# LED2.net
KiCad netlist of a schematic drawn in Altium Designer
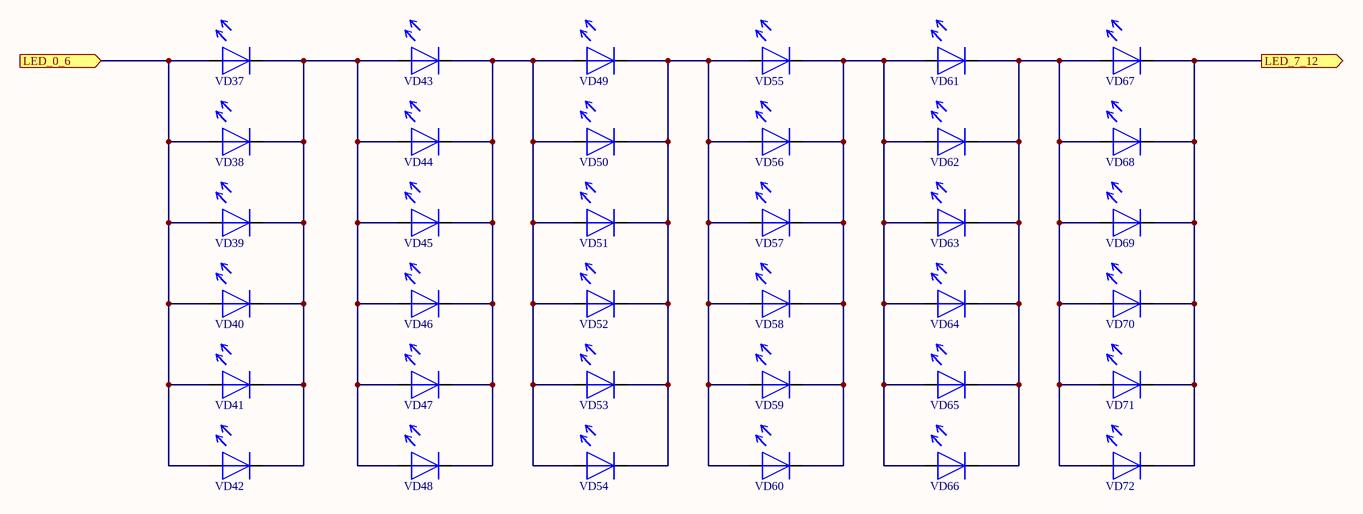
[diagram p0: LED2.SchDoc]

(export (version "E")
  (design (tool "Eeschema 10.0.6"))
  (components
    (comp (ref "VD37")
      (value "SPMWHT541MD5WAT0SB")
      (footprint "LED_Samsung")
      (libsource (lib "gprs_modem_2") (part "LED SPMWHT541MD5WAT0SB"))
    )
    (comp (ref "VD38")
      (value "SPMWHT541MD5WAT0SB")
      (footprint "LED_Samsung")
      (libsource (lib "gprs_modem_2") (part "LED SPMWHT541MD5WAT0SB"))
    )
    (comp (ref "VD39")
      (value "SPMWHT541MD5WAT0SB")
      (footprint "LED_Samsung")
      (libsource (lib "gprs_modem_2") (part "LED SPMWHT541MD5WAT0SB"))
    )
    (comp (ref "VD40")
      (value "SPMWHT541MD5WAT0SB")
      (footprint "LED_Samsung")
      (libsource (lib "gprs_modem_2") (part "LED SPMWHT541MD5WAT0SB"))
    )
    (comp (ref "VD41")
      (value "SPMWHT541MD5WAT0SB")
      (footprint "LED_Samsung")
      (libsource (lib "gprs_modem_2") (part "LED SPMWHT541MD5WAT0SB"))
    )
    (comp (ref "VD42")
      (value "SPMWHT541MD5WAT0SB")
      (footprint "LED_Samsung")
      (libsource (lib "gprs_modem_2") (part "LED SPMWHT541MD5WAT0SB"))
    )
    (comp (ref "VD43")
      (value "SPMWHT541MD5WAT0SB")
      (footprint "LED_Samsung")
      (libsource (lib "gprs_modem_2") (part "LED SPMWHT541MD5WAT0SB"))
    )
    (comp (ref "VD44")
      (value "SPMWHT541MD5WAT0SB")
      (footprint "LED_Samsung")
      (libsource (lib "gprs_modem_2") (part "LED SPMWHT541MD5WAT0SB"))
    )
    (comp (ref "VD45")
      (value "SPMWHT541MD5WAT0SB")
      (footprint "LED_Samsung")
      (libsource (lib "gprs_modem_2") (part "LED SPMWHT541MD5WAT0SB"))
    )
    (comp (ref "VD46")
      (value "SPMWHT541MD5WAT0SB")
      (footprint "LED_Samsung")
      (libsource (lib "gprs_modem_2") (part "LED SPMWHT541MD5WAT0SB"))
    )
    (comp (ref "VD47")
      (value "SPMWHT541MD5WAT0SB")
      (footprint "LED_Samsung")
      (libsource (lib "gprs_modem_2") (part "LED SPMWHT541MD5WAT0SB"))
    )
    (comp (ref "VD48")
      (value "SPMWHT541MD5WAT0SB")
      (footprint "LED_Samsung")
      (libsource (lib "gprs_modem_2") (part "LED SPMWHT541MD5WAT0SB"))
    )
    (comp (ref "VD49")
      (value "SPMWHT541MD5WAT0SB")
      (footprint "LED_Samsung")
      (libsource (lib "gprs_modem_2") (part "LED SPMWHT541MD5WAT0SB"))
    )
    (comp (ref "VD50")
      (value "SPMWHT541MD5WAT0SB")
      (footprint "LED_Samsung")
      (libsource (lib "gprs_modem_2") (part "LED SPMWHT541MD5WAT0SB"))
    )
    (comp (ref "VD51")
      (value "SPMWHT541MD5WAT0SB")
      (footprint "LED_Samsung")
      (libsource (lib "gprs_modem_2") (part "LED SPMWHT541MD5WAT0SB"))
    )
    (comp (ref "VD52")
      (value "SPMWHT541MD5WAT0SB")
      (footprint "LED_Samsung")
      (libsource (lib "gprs_modem_2") (part "LED SPMWHT541MD5WAT0SB"))
    )
    (comp (ref "VD53")
      (value "SPMWHT541MD5WAT0SB")
      (footprint "LED_Samsung")
      (libsource (lib "gprs_modem_2") (part "LED SPMWHT541MD5WAT0SB"))
    )
    (comp (ref "VD54")
      (value "SPMWHT541MD5WAT0SB")
      (footprint "LED_Samsung")
      (libsource (lib "gprs_modem_2") (part "LED SPMWHT541MD5WAT0SB"))
    )
    (comp (ref "VD55")
      (value "SPMWHT541MD5WAT0SB")
      (footprint "LED_Samsung")
      (libsource (lib "gprs_modem_2") (part "LED SPMWHT541MD5WAT0SB"))
    )
    (comp (ref "VD56")
      (value "SPMWHT541MD5WAT0SB")
      (footprint "LED_Samsung")
      (libsource (lib "gprs_modem_2") (part "LED SPMWHT541MD5WAT0SB"))
    )
    (comp (ref "VD57")
      (value "SPMWHT541MD5WAT0SB")
      (footprint "LED_Samsung")
      (libsource (lib "gprs_modem_2") (part "LED SPMWHT541MD5WAT0SB"))
    )
    (comp (ref "VD58")
      (value "SPMWHT541MD5WAT0SB")
      (footprint "LED_Samsung")
      (libsource (lib "gprs_modem_2") (part "LED SPMWHT541MD5WAT0SB"))
    )
    (comp (ref "VD59")
      (value "SPMWHT541MD5WAT0SB")
      (footprint "LED_Samsung")
      (libsource (lib "gprs_modem_2") (part "LED SPMWHT541MD5WAT0SB"))
    )
    (comp (ref "VD60")
      (value "SPMWHT541MD5WAT0SB")
      (footprint "LED_Samsung")
      (libsource (lib "gprs_modem_2") (part "LED SPMWHT541MD5WAT0SB"))
    )
    (comp (ref "VD61")
      (value "SPMWHT541MD5WAT0SB")
      (footprint "LED_Samsung")
      (libsource (lib "gprs_modem_2") (part "LED SPMWHT541MD5WAT0SB"))
    )
    (comp (ref "VD62")
      (value "SPMWHT541MD5WAT0SB")
      (footprint "LED_Samsung")
      (libsource (lib "gprs_modem_2") (part "LED SPMWHT541MD5WAT0SB"))
    )
    (comp (ref "VD63")
      (value "SPMWHT541MD5WAT0SB")
      (footprint "LED_Samsung")
      (libsource (lib "gprs_modem_2") (part "LED SPMWHT541MD5WAT0SB"))
    )
    (comp (ref "VD64")
      (value "SPMWHT541MD5WAT0SB")
      (footprint "LED_Samsung")
      (libsource (lib "gprs_modem_2") (part "LED SPMWHT541MD5WAT0SB"))
    )
    (comp (ref "VD65")
      (value "SPMWHT541MD5WAT0SB")
      (footprint "LED_Samsung")
      (libsource (lib "gprs_modem_2") (part "LED SPMWHT541MD5WAT0SB"))
    )
    (comp (ref "VD66")
      (value "SPMWHT541MD5WAT0SB")
      (footprint "LED_Samsung")
      (libsource (lib "gprs_modem_2") (part "LED SPMWHT541MD5WAT0SB"))
    )
    (comp (ref "VD67")
      (value "SPMWHT541MD5WAT0SB")
      (footprint "LED_Samsung")
      (libsource (lib "gprs_modem_2") (part "LED SPMWHT541MD5WAT0SB"))
    )
    (comp (ref "VD68")
      (value "SPMWHT541MD5WAT0SB")
      (footprint "LED_Samsung")
      (libsource (lib "gprs_modem_2") (part "LED SPMWHT541MD5WAT0SB"))
    )
    (comp (ref "VD69")
      (value "SPMWHT541MD5WAT0SB")
      (footprint "LED_Samsung")
      (libsource (lib "gprs_modem_2") (part "LED SPMWHT541MD5WAT0SB"))
    )
    (comp (ref "VD70")
      (value "SPMWHT541MD5WAT0SB")
      (footprint "LED_Samsung")
      (libsource (lib "gprs_modem_2") (part "LED SPMWHT541MD5WAT0SB"))
    )
    (comp (ref "VD71")
      (value "SPMWHT541MD5WAT0SB")
      (footprint "LED_Samsung")
      (libsource (lib "gprs_modem_2") (part "LED SPMWHT541MD5WAT0SB"))
    )
    (comp (ref "VD72")
      (value "SPMWHT541MD5WAT0SB")
      (footprint "LED_Samsung")
      (libsource (lib "gprs_modem_2") (part "LED SPMWHT541MD5WAT0SB"))
    )
  )
  (nets
    (net (code "1") (name "/LED_0_6") (class "Default")
      (node (ref "VD37") (pin "1") (pintype "passive"))
      (node (ref "VD38") (pin "1") (pintype "passive"))
      (node (ref "VD39") (pin "1") (pintype "passive"))
      (node (ref "VD40") (pin "1") (pintype "passive"))
      (node (ref "VD41") (pin "1") (pintype "passive"))
      (node (ref "VD42") (pin "1") (pintype "passive"))
    )
    (net (code "2") (name "/LED_7_12") (class "Default")
      (node (ref "VD67") (pin "2") (pintype "passive"))
      (node (ref "VD68") (pin "2") (pintype "passive"))
      (node (ref "VD69") (pin "2") (pintype "passive"))
      (node (ref "VD70") (pin "2") (pintype "passive"))
      (node (ref "VD71") (pin "2") (pintype "passive"))
      (node (ref "VD72") (pin "2") (pintype "passive"))
    )
    (net (code "3") (name "Net-(VD37-Pad2)") (class "Default")
      (node (ref "VD37") (pin "2") (pintype "passive"))
      (node (ref "VD38") (pin "2") (pintype "passive"))
      (node (ref "VD39") (pin "2") (pintype "passive"))
      (node (ref "VD40") (pin "2") (pintype "passive"))
      (node (ref "VD41") (pin "2") (pintype "passive"))
      (node (ref "VD42") (pin "2") (pintype "passive"))
      (node (ref "VD43") (pin "1") (pintype "passive"))
      (node (ref "VD44") (pin "1") (pintype "passive"))
      (node (ref "VD45") (pin "1") (pintype "passive"))
      (node (ref "VD46") (pin "1") (pintype "passive"))
      (node (ref "VD47") (pin "1") (pintype "passive"))
      (node (ref "VD48") (pin "1") (pintype "passive"))
    )
    (net (code "4") (name "Net-(VD43-Pad2)") (class "Default")
      (node (ref "VD43") (pin "2") (pintype "passive"))
      (node (ref "VD44") (pin "2") (pintype "passive"))
      (node (ref "VD45") (pin "2") (pintype "passive"))
      (node (ref "VD46") (pin "2") (pintype "passive"))
      (node (ref "VD47") (pin "2") (pintype "passive"))
      (node (ref "VD48") (pin "2") (pintype "passive"))
      (node (ref "VD49") (pin "1") (pintype "passive"))
      (node (ref "VD50") (pin "1") (pintype "passive"))
      (node (ref "VD51") (pin "1") (pintype "passive"))
      (node (ref "VD52") (pin "1") (pintype "passive"))
      (node (ref "VD53") (pin "1") (pintype "passive"))
      (node (ref "VD54") (pin "1") (pintype "passive"))
    )
    (net (code "5") (name "Net-(VD49-Pad2)") (class "Default")
      (node (ref "VD49") (pin "2") (pintype "passive"))
      (node (ref "VD50") (pin "2") (pintype "passive"))
      (node (ref "VD51") (pin "2") (pintype "passive"))
      (node (ref "VD52") (pin "2") (pintype "passive"))
      (node (ref "VD53") (pin "2") (pintype "passive"))
      (node (ref "VD54") (pin "2") (pintype "passive"))
      (node (ref "VD55") (pin "1") (pintype "passive"))
      (node (ref "VD56") (pin "1") (pintype "passive"))
      (node (ref "VD57") (pin "1") (pintype "passive"))
      (node (ref "VD58") (pin "1") (pintype "passive"))
      (node (ref "VD59") (pin "1") (pintype "passive"))
      (node (ref "VD60") (pin "1") (pintype "passive"))
    )
    (net (code "6") (name "Net-(VD55-Pad2)") (class "Default")
      (node (ref "VD55") (pin "2") (pintype "passive"))
      (node (ref "VD56") (pin "2") (pintype "passive"))
      (node (ref "VD57") (pin "2") (pintype "passive"))
      (node (ref "VD58") (pin "2") (pintype "passive"))
      (node (ref "VD59") (pin "2") (pintype "passive"))
      (node (ref "VD60") (pin "2") (pintype "passive"))
      (node (ref "VD61") (pin "1") (pintype "passive"))
      (node (ref "VD62") (pin "1") (pintype "passive"))
      (node (ref "VD63") (pin "1") (pintype "passive"))
      (node (ref "VD64") (pin "1") (pintype "passive"))
      (node (ref "VD65") (pin "1") (pintype "passive"))
      (node (ref "VD66") (pin "1") (pintype "passive"))
    )
    (net (code "7") (name "Net-(VD61-Pad2)") (class "Default")
      (node (ref "VD61") (pin "2") (pintype "passive"))
      (node (ref "VD62") (pin "2") (pintype "passive"))
      (node (ref "VD63") (pin "2") (pintype "passive"))
      (node (ref "VD64") (pin "2") (pintype "passive"))
      (node (ref "VD65") (pin "2") (pintype "passive"))
      (node (ref "VD66") (pin "2") (pintype "passive"))
      (node (ref "VD67") (pin "1") (pintype "passive"))
      (node (ref "VD68") (pin "1") (pintype "passive"))
      (node (ref "VD69") (pin "1") (pintype "passive"))
      (node (ref "VD70") (pin "1") (pintype "passive"))
      (node (ref "VD71") (pin "1") (pintype "passive"))
      (node (ref "VD72") (pin "1") (pintype "passive"))
    )
  )
)
